# PIC16F687_7segLED.net
KiCad netlist of a schematic drawn in EAGLE
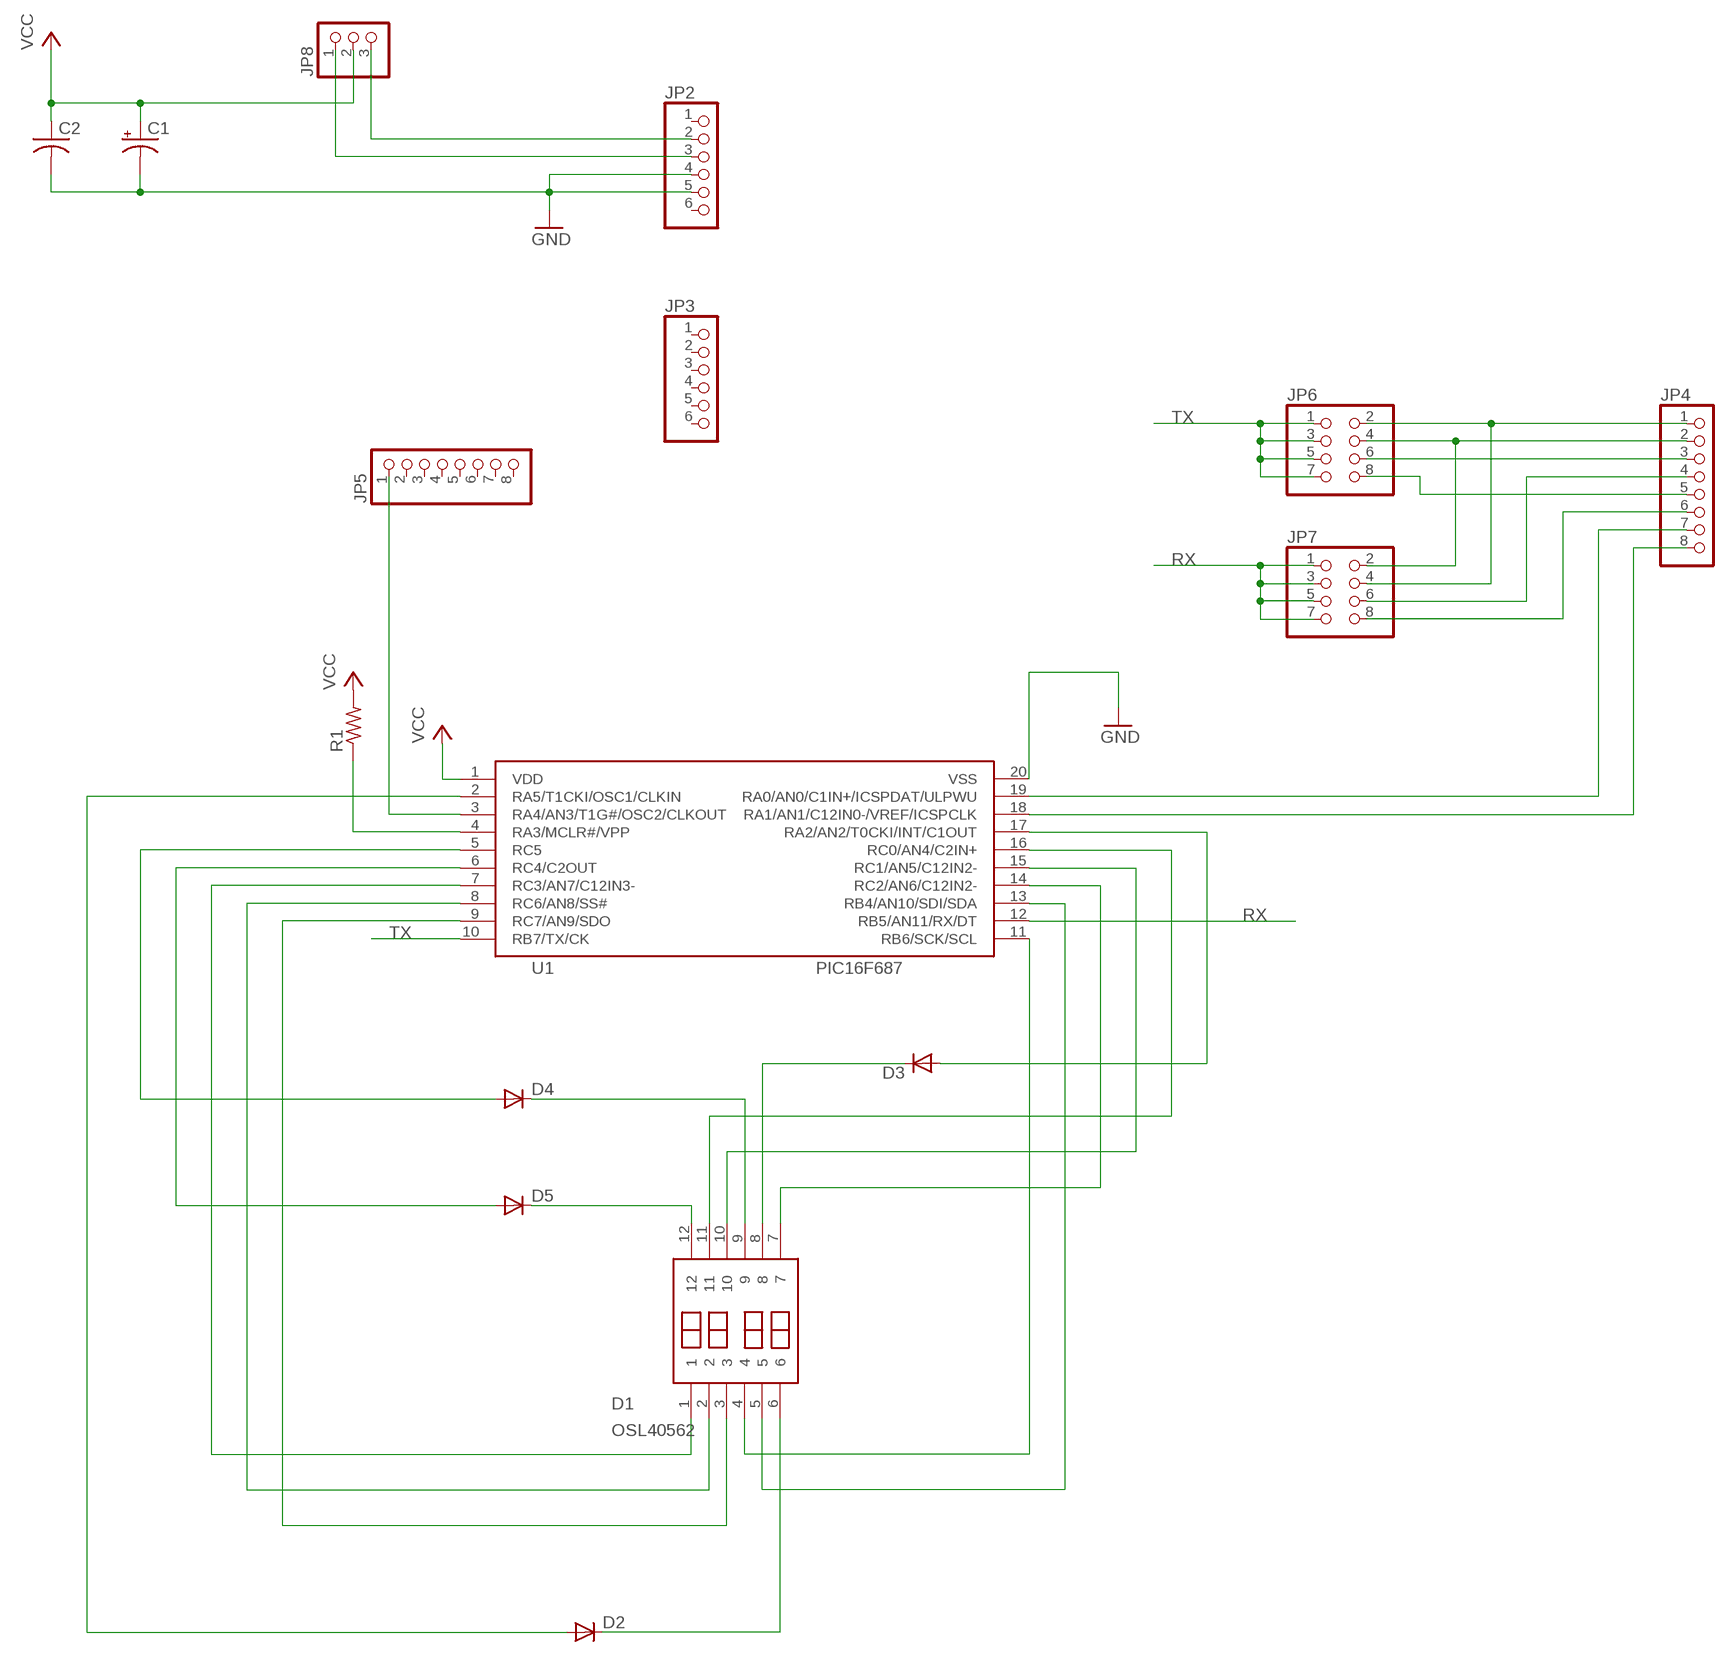
[diagram p0: schematic, sheet 1]

(export (version "E")
  (design (tool "Eeschema 10.0.6"))
  (components
    (comp (ref "C1")
      (value "CPOL-US")
      (footprint "eagle-import:CPOL-US")
      (libsource (lib "eagle-import") (part "CPOL-US"))
    )
    (comp (ref "C2")
      (value "CAP")
      (footprint "eagle-import:C025-040X050")
      (libsource (lib "eagle-import") (part "CAP"))
    )
    (comp (ref "D1")
      (value "OSL40562")
      (footprint "eagle-import:OSL40562")
      (libsource (lib "eagle-import") (part "OSL40562"))
    )
    (comp (ref "D2")
      (value "DIODE-01")
      (footprint "eagle-import:0204_D")
      (libsource (lib "eagle-import") (part "DIODE-01"))
    )
    (comp (ref "D3")
      (value "DIODE-01")
      (footprint "eagle-import:0204_D")
      (libsource (lib "eagle-import") (part "DIODE-01"))
    )
    (comp (ref "D4")
      (value "DIODE-01")
      (footprint "eagle-import:0204_D")
      (libsource (lib "eagle-import") (part "DIODE-01"))
    )
    (comp (ref "D5")
      (value "DIODE-01")
      (footprint "eagle-import:0204_D")
      (libsource (lib "eagle-import") (part "DIODE-01"))
    )
    (comp (ref "JP2")
      (value "PINHD-1X6")
      (footprint "eagle-import:1X06")
      (libsource (lib "eagle-import") (part "PINHD-1X6"))
    )
    (comp (ref "JP3")
      (value "PINHD-1X6")
      (footprint "eagle-import:1X06")
      (libsource (lib "eagle-import") (part "PINHD-1X6"))
    )
    (comp (ref "JP4")
      (value "PINHD-1X8")
      (footprint "eagle-import:1X08")
      (libsource (lib "eagle-import") (part "PINHD-1X8"))
    )
    (comp (ref "JP5")
      (value "PINHD-1X8")
      (footprint "eagle-import:1X08")
      (libsource (lib "eagle-import") (part "PINHD-1X8"))
    )
    (comp (ref "JP6")
      (value "PINHD-2X4")
      (footprint "eagle-import:2X04")
      (libsource (lib "eagle-import") (part "PINHD-2X4"))
    )
    (comp (ref "JP7")
      (value "PINHD-2X4")
      (footprint "eagle-import:2X04")
      (libsource (lib "eagle-import") (part "PINHD-2X4"))
    )
    (comp (ref "JP8")
      (value "PINHD-1X3")
      (footprint "eagle-import:1X03")
      (libsource (lib "eagle-import") (part "PINHD-1X3"))
    )
    (comp (ref "R1")
      (value "R-US-01")
      (footprint "eagle-import:0204V")
      (libsource (lib "eagle-import") (part "R-US-01"))
    )
    (comp (ref "U1")
      (value "PIC16F687")
      (footprint "eagle-import:DIP20")
      (libsource (lib "eagle-import") (part "PIC16F687"))
    )
  )
  (nets
    (net (code "1") (name "/RX") (class "Default")
      (node (ref "JP7") (pin "1") (pinfunction "1_1") (pintype "passive"))
      (node (ref "JP7") (pin "3") (pinfunction "3_3") (pintype "passive"))
      (node (ref "JP7") (pin "5") (pinfunction "5_5") (pintype "passive"))
      (node (ref "JP7") (pin "7") (pinfunction "7_7") (pintype "passive"))
      (node (ref "U1") (pin "12") (pinfunction "RB5/AN11/RX/DT_12") (pintype "bidirectional"))
    )
    (net (code "2") (name "/TX") (class "Default")
      (node (ref "JP6") (pin "1") (pinfunction "1_1") (pintype "passive"))
      (node (ref "JP6") (pin "3") (pinfunction "3_3") (pintype "passive"))
      (node (ref "JP6") (pin "5") (pinfunction "5_5") (pintype "passive"))
      (node (ref "JP6") (pin "7") (pinfunction "7_7") (pintype "passive"))
      (node (ref "U1") (pin "10") (pinfunction "RB7/TX/CK_10") (pintype "bidirectional"))
    )
    (net (code "3") (name "GND") (class "Default")
      (node (ref "C1") (pin "-") (pinfunction "-_-") (pintype "passive"))
      (node (ref "C2") (pin "2") (pinfunction "2_2") (pintype "passive"))
      (node (ref "JP2") (pin "4") (pinfunction "4_4") (pintype "passive"))
      (node (ref "JP2") (pin "5") (pinfunction "5_5") (pintype "passive"))
      (node (ref "U1") (pin "20") (pinfunction "VSS_20") (pintype "power_in"))
    )
    (net (code "4") (name "Net-(D2-A)") (class "Default")
      (node (ref "D2") (pin "1") (pinfunction "A_1") (pintype "passive"))
      (node (ref "U1") (pin "2") (pinfunction "RA5/T1CKI/OSC1/CLKIN_2") (pintype "bidirectional"))
    )
    (net (code "5") (name "Net-(D2-C)") (class "Default")
      (node (ref "D1") (pin "6") (pinfunction "6_6") (pintype "bidirectional"))
      (node (ref "D2") (pin "2") (pinfunction "C_2") (pintype "passive"))
    )
    (net (code "6") (name "Net-(D3-A)") (class "Default")
      (node (ref "D3") (pin "1") (pinfunction "A_1") (pintype "passive"))
      (node (ref "U1") (pin "17") (pinfunction "RA2/AN2/T0CKI/INT/C1OUT_17") (pintype "bidirectional"))
    )
    (net (code "7") (name "Net-(D3-C)") (class "Default")
      (node (ref "D1") (pin "8") (pinfunction "8_8") (pintype "bidirectional"))
      (node (ref "D3") (pin "2") (pinfunction "C_2") (pintype "passive"))
    )
    (net (code "8") (name "Net-(D4-A)") (class "Default")
      (node (ref "D4") (pin "1") (pinfunction "A_1") (pintype "passive"))
      (node (ref "U1") (pin "5") (pinfunction "RC5_5") (pintype "bidirectional"))
    )
    (net (code "9") (name "Net-(D4-C)") (class "Default")
      (node (ref "D1") (pin "9") (pinfunction "9_9") (pintype "bidirectional"))
      (node (ref "D4") (pin "2") (pinfunction "C_2") (pintype "passive"))
    )
    (net (code "10") (name "Net-(D5-A)") (class "Default")
      (node (ref "D5") (pin "1") (pinfunction "A_1") (pintype "passive"))
      (node (ref "U1") (pin "6") (pinfunction "RC4/C2OUT_6") (pintype "bidirectional"))
    )
    (net (code "11") (name "Net-(D5-C)") (class "Default")
      (node (ref "D1") (pin "12") (pinfunction "12_12") (pintype "bidirectional"))
      (node (ref "D5") (pin "2") (pinfunction "C_2") (pintype "passive"))
    )
    (net (code "12") (name "Net-(JP2-Pad2)") (class "Default")
      (node (ref "JP2") (pin "2") (pinfunction "2_2") (pintype "passive"))
      (node (ref "JP8") (pin "3") (pinfunction "3_3") (pintype "passive"))
    )
    (net (code "13") (name "Net-(JP2-Pad3)") (class "Default")
      (node (ref "JP2") (pin "3") (pinfunction "3_3") (pintype "passive"))
      (node (ref "JP8") (pin "1") (pinfunction "1_1") (pintype "passive"))
    )
    (net (code "14") (name "Net-(JP4-Pad1)") (class "Default")
      (node (ref "JP4") (pin "1") (pinfunction "1_1") (pintype "passive"))
      (node (ref "JP6") (pin "2") (pinfunction "2_2") (pintype "passive"))
      (node (ref "JP7") (pin "4") (pinfunction "4_4") (pintype "passive"))
    )
    (net (code "15") (name "Net-(JP4-Pad2)") (class "Default")
      (node (ref "JP4") (pin "2") (pinfunction "2_2") (pintype "passive"))
      (node (ref "JP6") (pin "4") (pinfunction "4_4") (pintype "passive"))
      (node (ref "JP7") (pin "2") (pinfunction "2_2") (pintype "passive"))
    )
    (net (code "16") (name "Net-(JP4-Pad3)") (class "Default")
      (node (ref "JP4") (pin "3") (pinfunction "3_3") (pintype "passive"))
      (node (ref "JP6") (pin "6") (pinfunction "6_6") (pintype "passive"))
    )
    (net (code "17") (name "Net-(JP4-Pad4)") (class "Default")
      (node (ref "JP4") (pin "4") (pinfunction "4_4") (pintype "passive"))
      (node (ref "JP7") (pin "6") (pinfunction "6_6") (pintype "passive"))
    )
    (net (code "18") (name "Net-(JP4-Pad5)") (class "Default")
      (node (ref "JP4") (pin "5") (pinfunction "5_5") (pintype "passive"))
      (node (ref "JP6") (pin "8") (pinfunction "8_8") (pintype "passive"))
    )
    (net (code "19") (name "Net-(JP4-Pad6)") (class "Default")
      (node (ref "JP4") (pin "6") (pinfunction "6_6") (pintype "passive"))
      (node (ref "JP7") (pin "8") (pinfunction "8_8") (pintype "passive"))
    )
    (net (code "20") (name "Net-(U1-RA0{slash}AN0{slash}C1IN+{slash}ICSPDAT{slash}ULPWU)") (class "Default")
      (node (ref "JP4") (pin "7") (pinfunction "7_7") (pintype "passive"))
      (node (ref "U1") (pin "19") (pinfunction "RA0/AN0/C1IN+/ICSPDAT/ULPWU_19") (pintype "bidirectional"))
    )
    (net (code "21") (name "Net-(U1-RA1{slash}AN1{slash}C12IN0-{slash}VREF{slash}ICSPCLK)") (class "Default")
      (node (ref "JP4") (pin "8") (pinfunction "8_8") (pintype "passive"))
      (node (ref "U1") (pin "18") (pinfunction "RA1/AN1/C12IN0-/VREF/ICSPCLK_18") (pintype "bidirectional"))
    )
    (net (code "22") (name "Net-(U1-RA3{slash}MCLR#{slash}VPP)") (class "Default")
      (node (ref "R1") (pin "1") (pinfunction "1_1") (pintype "passive"))
      (node (ref "U1") (pin "4") (pinfunction "RA3/MCLR#/VPP_4") (pintype "bidirectional"))
    )
    (net (code "23") (name "Net-(U1-RA4{slash}AN3{slash}T1G#{slash}OSC2{slash}CLKOUT)") (class "Default")
      (node (ref "JP5") (pin "1") (pinfunction "1_1") (pintype "passive"))
      (node (ref "U1") (pin "3") (pinfunction "RA4/AN3/T1G#/OSC2/CLKOUT_3") (pintype "bidirectional"))
    )
    (net (code "24") (name "Net-(U1-RB4{slash}AN10{slash}SDI{slash}SDA)") (class "Default")
      (node (ref "D1") (pin "5") (pinfunction "5_5") (pintype "bidirectional"))
      (node (ref "U1") (pin "13") (pinfunction "RB4/AN10/SDI/SDA_13") (pintype "bidirectional"))
    )
    (net (code "25") (name "Net-(U1-RB6{slash}SCK{slash}SCL)") (class "Default")
      (node (ref "D1") (pin "4") (pinfunction "4_4") (pintype "bidirectional"))
      (node (ref "U1") (pin "11") (pinfunction "RB6/SCK/SCL_11") (pintype "bidirectional"))
    )
    (net (code "26") (name "Net-(U1-RC0{slash}AN4{slash}C2IN+)") (class "Default")
      (node (ref "D1") (pin "11") (pinfunction "11_11") (pintype "bidirectional"))
      (node (ref "U1") (pin "16") (pinfunction "RC0/AN4/C2IN+_16") (pintype "bidirectional"))
    )
    (net (code "27") (name "Net-(U1-RC1{slash}AN5{slash}C12IN2-)") (class "Default")
      (node (ref "D1") (pin "10") (pinfunction "10_10") (pintype "bidirectional"))
      (node (ref "U1") (pin "15") (pinfunction "RC1/AN5/C12IN2-_15") (pintype "bidirectional"))
    )
    (net (code "28") (name "Net-(U1-RC2{slash}AN6{slash}C12IN2-)") (class "Default")
      (node (ref "D1") (pin "7") (pinfunction "7_7") (pintype "bidirectional"))
      (node (ref "U1") (pin "14") (pinfunction "RC2/AN6/C12IN2-_14") (pintype "bidirectional"))
    )
    (net (code "29") (name "Net-(U1-RC3{slash}AN7{slash}C12IN3-)") (class "Default")
      (node (ref "D1") (pin "1") (pinfunction "1_1") (pintype "bidirectional"))
      (node (ref "U1") (pin "7") (pinfunction "RC3/AN7/C12IN3-_7") (pintype "bidirectional"))
    )
    (net (code "30") (name "Net-(U1-RC6{slash}AN8{slash}SS#)") (class "Default")
      (node (ref "D1") (pin "2") (pinfunction "2_2") (pintype "bidirectional"))
      (node (ref "U1") (pin "8") (pinfunction "RC6/AN8/SS#_8") (pintype "bidirectional"))
    )
    (net (code "31") (name "Net-(U1-RC7{slash}AN9{slash}SDO)") (class "Default")
      (node (ref "D1") (pin "3") (pinfunction "3_3") (pintype "bidirectional"))
      (node (ref "U1") (pin "9") (pinfunction "RC7/AN9/SDO_9") (pintype "bidirectional"))
    )
    (net (code "32") (name "VCC") (class "Default")
      (node (ref "C1") (pin "+") (pinfunction "+_+") (pintype "passive"))
      (node (ref "C2") (pin "1") (pinfunction "1_1") (pintype "passive"))
      (node (ref "JP8") (pin "2") (pinfunction "2_2") (pintype "passive"))
      (node (ref "R1") (pin "2") (pinfunction "2_2") (pintype "passive"))
      (node (ref "U1") (pin "1") (pinfunction "VDD_1") (pintype "power_in"))
    )
    (net (code "33") (name "unconnected-(JP2-Pad1)") (class "Default")
      (node (ref "JP2") (pin "1") (pinfunction "1_1") (pintype "passive"))
    )
    (net (code "34") (name "unconnected-(JP2-Pad6)") (class "Default")
      (node (ref "JP2") (pin "6") (pinfunction "6_6") (pintype "passive"))
    )
    (net (code "35") (name "unconnected-(JP3-Pad1)") (class "Default")
      (node (ref "JP3") (pin "1") (pinfunction "1_1") (pintype "passive"))
    )
    (net (code "36") (name "unconnected-(JP3-Pad2)") (class "Default")
      (node (ref "JP3") (pin "2") (pinfunction "2_2") (pintype "passive"))
    )
    (net (code "37") (name "unconnected-(JP3-Pad3)") (class "Default")
      (node (ref "JP3") (pin "3") (pinfunction "3_3") (pintype "passive"))
    )
    (net (code "38") (name "unconnected-(JP3-Pad4)") (class "Default")
      (node (ref "JP3") (pin "4") (pinfunction "4_4") (pintype "passive"))
    )
    (net (code "39") (name "unconnected-(JP3-Pad5)") (class "Default")
      (node (ref "JP3") (pin "5") (pinfunction "5_5") (pintype "passive"))
    )
    (net (code "40") (name "unconnected-(JP3-Pad6)") (class "Default")
      (node (ref "JP3") (pin "6") (pinfunction "6_6") (pintype "passive"))
    )
    (net (code "41") (name "unconnected-(JP5-Pad2)") (class "Default")
      (node (ref "JP5") (pin "2") (pinfunction "2_2") (pintype "passive"))
    )
    (net (code "42") (name "unconnected-(JP5-Pad3)") (class "Default")
      (node (ref "JP5") (pin "3") (pinfunction "3_3") (pintype "passive"))
    )
    (net (code "43") (name "unconnected-(JP5-Pad4)") (class "Default")
      (node (ref "JP5") (pin "4") (pinfunction "4_4") (pintype "passive"))
    )
    (net (code "44") (name "unconnected-(JP5-Pad5)") (class "Default")
      (node (ref "JP5") (pin "5") (pinfunction "5_5") (pintype "passive"))
    )
    (net (code "45") (name "unconnected-(JP5-Pad6)") (class "Default")
      (node (ref "JP5") (pin "6") (pinfunction "6_6") (pintype "passive"))
    )
    (net (code "46") (name "unconnected-(JP5-Pad7)") (class "Default")
      (node (ref "JP5") (pin "7") (pinfunction "7_7") (pintype "passive"))
    )
    (net (code "47") (name "unconnected-(JP5-Pad8)") (class "Default")
      (node (ref "JP5") (pin "8") (pinfunction "8_8") (pintype "passive"))
    )
  )
)
